# SIM808.net
KiCad netlist of a schematic drawn in Altium Designer
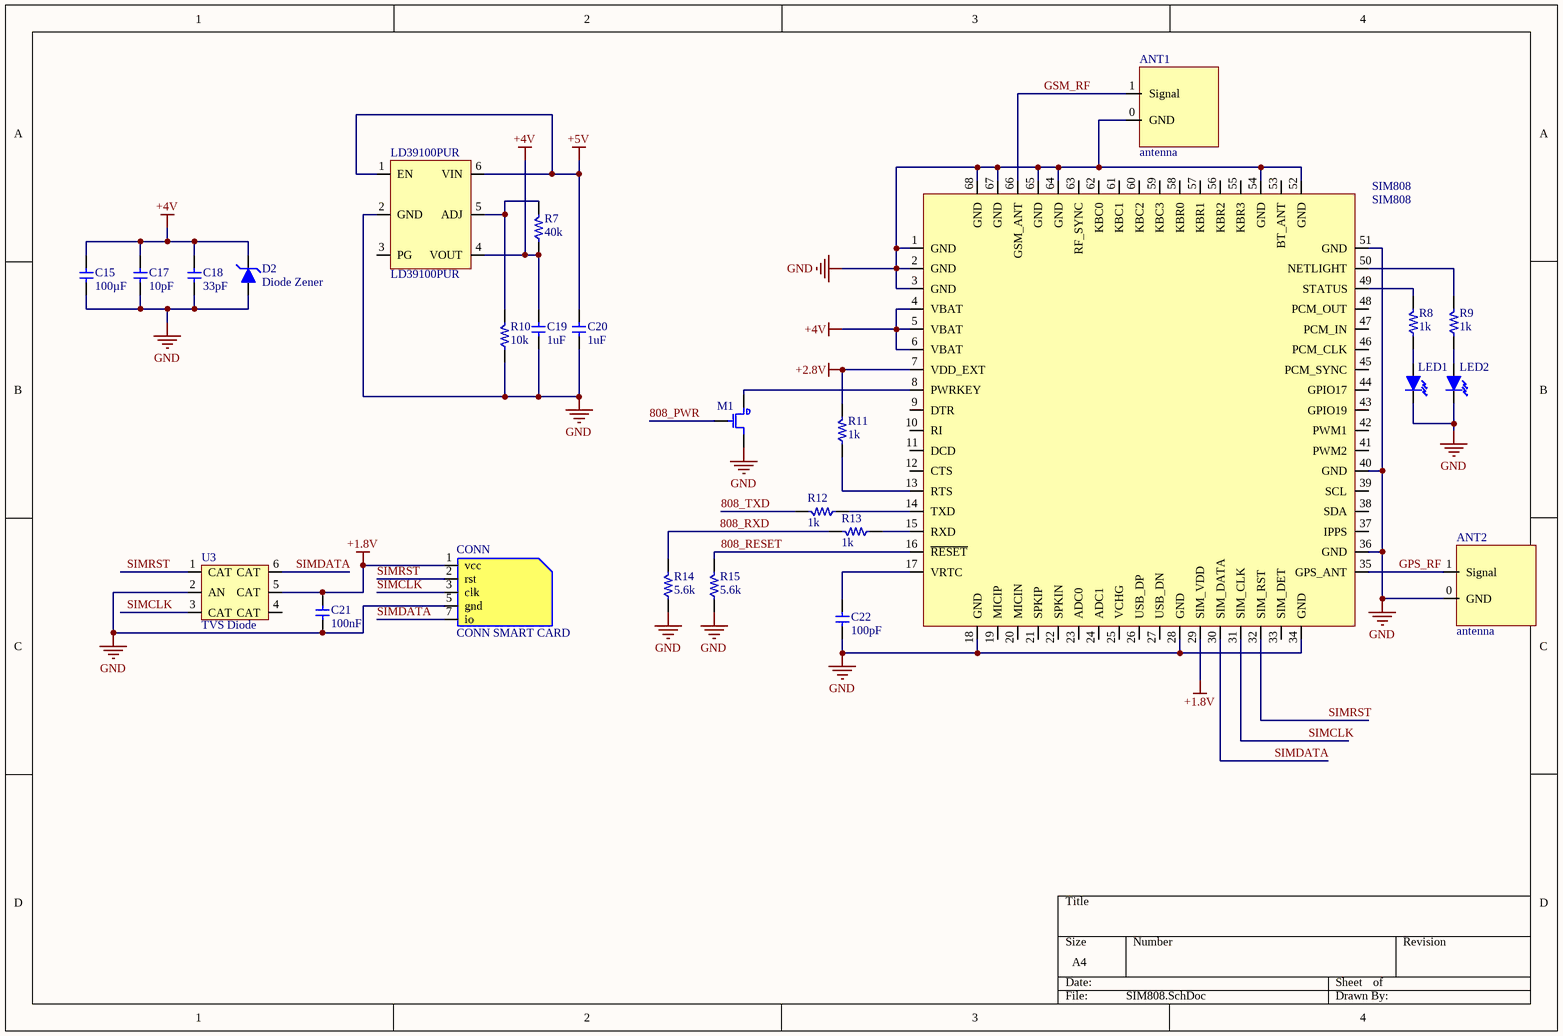
[diagram p0: SIM808.SchDoc]

(export (version "E")
  (design (tool "Eeschema 10.0.6"))
  (components
    (comp (ref "ANT1")
      (value "antenna")
      (footprint "uFL")
      (description "uFL SMT Antenna Connector")
      (fields (field (name "MFR") "adafruit"))
      (libsource (lib "uFLAntenna") (part "antenna"))
    )
    (comp (ref "ANT2")
      (value "antenna")
      (footprint "uFL")
      (description "uFL SMT Antenna Connector")
      (fields (field (name "MFR") "adafruit"))
      (libsource (lib "uFLAntenna") (part "antenna"))
    )
    (comp (ref "C15")
      (value "Cap Cer 100uF")
      (footprint "Cap 1210")
      (description "CAP CER 100UF 10V X5R 1210")
      (fields
        (field (name "MANUFACTURER") "Taiyo Yuden")
        (field (name "MANUFACTURER PART NUMBER") "LMK325ABJ107MM-P")
        (field (name "CAPACITANCE") "100µF")
      )
      (libsource (lib "SIM808") (part "LMK325ABJ107MM-P"))
    )
    (comp (ref "C17")
      (value "10pF")
      (footprint "0805")
      (description "Generic capacitor")
      (fields (field (name "Comment") "Generic Capacitor"))
      (libsource (lib "PowerCircuit") (part "Capacitor"))
    )
    (comp (ref "C18")
      (value "33pF")
      (footprint "0805")
      (description "Generic capacitor")
      (fields (field (name "Comment") "Generic Capacitor"))
      (libsource (lib "PowerCircuit") (part "Capacitor"))
    )
    (comp (ref "C19")
      (value "1uF")
      (footprint "0805")
      (description "Generic capacitor")
      (fields (field (name "Comment") "Generic Capacitor"))
      (libsource (lib "PowerCircuit") (part "Capacitor"))
    )
    (comp (ref "C20")
      (value "1uF")
      (footprint "0805")
      (description "Generic capacitor")
      (fields (field (name "Comment") "Generic Capacitor"))
      (libsource (lib "PowerCircuit") (part "Capacitor"))
    )
    (comp (ref "C21")
      (value "100nF")
      (footprint "0805")
      (description "Generic capacitor")
      (fields (field (name "Comment") "Generic Capacitor"))
      (libsource (lib "PowerCircuit") (part "Capacitor"))
    )
    (comp (ref "C22")
      (value "100pF")
      (footprint "0805")
      (description "Generic capacitor")
      (fields (field (name "Comment") "Generic Capacitor"))
      (libsource (lib "PowerCircuit") (part "Capacitor"))
    )
    (comp (ref "CONN")
      (value "CONN SMART CARD")
      (footprint "CONN SMART CARD")
      (fields
        (field (name "MANUFACTURER") "Wurth Electronics Inc")
        (field (name "MANUFACTURER PART NUMBER") "693022010811")
      )
      (libsource (lib "SIM808") (part "CONN SMART CARD"))
    )
    (comp (ref "D2")
      (value "Diode Zener")
      (footprint "Diode Zener")
      (description "DIODE ZENER 5.1V 500MW SOD123")
      (fields
        (field (name "MANUFACTURER") "ON Semiconductor")
        (field (name "MANUFACTURER PART NUMBER") "MMSZ5231BT1G")
      )
      (libsource (lib "SIM808") (part "MMSZ5231BT1G"))
    )
    (comp (ref "LD39100PUR")
      (value "LD39100PUR")
      (footprint "LD39100PUR")
      (description "Adjustable linear voltage regulator")
      (fields (field (name "MFR") "ST"))
      (libsource (lib "SIM808") (part "LD39100PUR"))
    )
    (comp (ref "LED1")
      (value "Led Red")
      (footprint "0805 LED")
      (description "LED RED CLEAR 0805 SMD")
      (fields
        (field (name "MANUFACTURER") "Lite-On Inc.")
        (field (name "MANUFACTURER PART NUMBER") "LTST-C171EKT")
      )
      (libsource (lib "SIM808") (part "LTST-C171EKT"))
    )
    (comp (ref "LED2")
      (value "Led Green")
      (footprint "0805 LED")
      (description "LED GREEN CLEAR 0805 SMD")
      (fields
        (field (name "MANUFACTURER") "Lite-On Inc.")
        (field (name "MANUFACTURER PART NUMBER") "LTST-C170GKT")
      )
      (libsource (lib "SIM808") (part "LTST-C170GKT"))
    )
    (comp (ref "M1")
      (value "N-CH Mosfet Switch")
      (footprint "SOT32-3")
      (description "MOSFET N-CH 20V 1.05A SOT23")
      (fields
        (field (name "MANUFACTURER") "NXP USA Inc.")
        (field (name "MANUFACTURER PART NUMBER") "BSH105,215")
      )
      (libsource (lib "SIM808") (part "BSH105,215"))
    )
    (comp (ref "R7")
      (value "40k")
      (footprint "0805")
      (description "Generic Resistor")
      (fields (field (name "Comment") "Resistor"))
      (libsource (lib "PowerCircuit") (part "Resistor"))
    )
    (comp (ref "R8")
      (value "1k")
      (footprint "0805")
      (description "Generic Resistor")
      (fields (field (name "Comment") "Resistor"))
      (libsource (lib "PowerCircuit") (part "Resistor"))
    )
    (comp (ref "R9")
      (value "1k")
      (footprint "0805")
      (description "Generic Resistor")
      (fields (field (name "Comment") "Resistor"))
      (libsource (lib "PowerCircuit") (part "Resistor"))
    )
    (comp (ref "R10")
      (value "10k")
      (footprint "0805")
      (description "Generic Resistor")
      (fields (field (name "Comment") "Resistor"))
      (libsource (lib "PowerCircuit") (part "Resistor"))
    )
    (comp (ref "R11")
      (value "1k")
      (footprint "0805")
      (description "Generic Resistor")
      (fields (field (name "Comment") "Resistor"))
      (libsource (lib "PowerCircuit") (part "Resistor"))
    )
    (comp (ref "R12")
      (value "1k")
      (footprint "0805")
      (description "Generic Resistor")
      (fields (field (name "Comment") "Resistor"))
      (libsource (lib "PowerCircuit") (part "Resistor"))
    )
    (comp (ref "R13")
      (value "1k")
      (footprint "0805")
      (description "Generic Resistor")
      (fields (field (name "Comment") "Resistor"))
      (libsource (lib "PowerCircuit") (part "Resistor"))
    )
    (comp (ref "R14")
      (value "5.6k")
      (footprint "0805")
      (description "Generic Resistor")
      (fields (field (name "Comment") "Resistor"))
      (libsource (lib "PowerCircuit") (part "Resistor"))
    )
    (comp (ref "R15")
      (value "5.6k")
      (footprint "0805")
      (description "Generic Resistor")
      (fields (field (name "Comment") "Resistor"))
      (libsource (lib "PowerCircuit") (part "Resistor"))
    )
    (comp (ref "SIM808")
      (value "SIM808")
      (footprint "SIM808")
      (description "SIM808 GSM + GPRS + GPS Cellular Module")
      (fields (field (name "MFR") "SimCom"))
      (libsource (lib "SIM808") (part "SIM808"))
    )
    (comp (ref "U3")
      (value "TVS Diode")
      (footprint "SMF05CT2G")
      (description "TVS DIODE 5VWM 12.5VC SOT363")
      (fields
        (field (name "MANUFACTURER") "ON Semiconductor")
        (field (name "MANUFACTURER PART NUMBER") "SMF05CT2G")
      )
      (libsource (lib "SIM808") (part "SMF05CT2G"))
    )
  )
  (nets
    (net (code "1") (name "+1.8V") (class "Default")
      (node (ref "C21") (pin "1") (pinfunction "1_1") (pintype "passive"))
      (node (ref "CONN") (pin "1") (pinfunction "vcc_1") (pintype "passive"))
      (node (ref "SIM808") (pin "29") (pinfunction "SIM_VDD_29") (pintype "passive"))
      (node (ref "U3") (pin "5") (pinfunction "CAT_5") (pintype "passive"))
    )
    (net (code "2") (name "+2.8V") (class "Default")
      (node (ref "R11") (pin "2") (pinfunction "2_2") (pintype "passive"))
      (node (ref "SIM808") (pin "7") (pinfunction "VDD_EXT_7") (pintype "passive"))
    )
    (net (code "3") (name "+4V") (class "Default")
      (node (ref "C15") (pin "1") (pinfunction "1_1") (pintype "passive"))
      (node (ref "C17") (pin "1") (pinfunction "1_1") (pintype "passive"))
      (node (ref "C18") (pin "1") (pinfunction "1_1") (pintype "passive"))
      (node (ref "C19") (pin "2") (pinfunction "2_2") (pintype "passive"))
      (node (ref "D2") (pin "1") (pinfunction "1_1") (pintype "passive"))
      (node (ref "LD39100PUR") (pin "4") (pinfunction "VOUT_4") (pintype "passive"))
      (node (ref "R7") (pin "1") (pinfunction "1_1") (pintype "passive"))
      (node (ref "SIM808") (pin "4") (pinfunction "VBAT_4") (pintype "passive"))
      (node (ref "SIM808") (pin "5") (pinfunction "VBAT_5") (pintype "passive"))
      (node (ref "SIM808") (pin "6") (pinfunction "VBAT_6") (pintype "passive"))
    )
    (net (code "4") (name "+5V") (class "Default")
      (node (ref "C20") (pin "1") (pinfunction "1_1") (pintype "passive"))
      (node (ref "LD39100PUR") (pin "1") (pinfunction "EN_1") (pintype "passive"))
      (node (ref "LD39100PUR") (pin "6") (pinfunction "VIN_6") (pintype "passive"))
    )
    (net (code "5") (name "/808_PWR") (class "Default")
      (node (ref "M1") (pin "1") (pinfunction "G_1") (pintype "passive"))
    )
    (net (code "6") (name "/808_RESET") (class "Default")
      (node (ref "R15") (pin "2") (pinfunction "2_2") (pintype "passive"))
      (node (ref "SIM808") (pin "16") (pinfunction "~{RESET}_16") (pintype "passive"))
    )
    (net (code "7") (name "/808_RXD") (class "Default")
      (node (ref "R13") (pin "2") (pinfunction "2_2") (pintype "passive"))
      (node (ref "R14") (pin "2") (pinfunction "2_2") (pintype "passive"))
    )
    (net (code "8") (name "/808_TXD") (class "Default")
      (node (ref "R12") (pin "2") (pinfunction "2_2") (pintype "passive"))
    )
    (net (code "9") (name "/GPS_RF") (class "Default")
      (node (ref "ANT2") (pin "1") (pinfunction "Signal_1") (pintype "passive"))
      (node (ref "SIM808") (pin "35") (pinfunction "GPS_ANT_35") (pintype "passive"))
    )
    (net (code "10") (name "/GSM_RF") (class "Default")
      (node (ref "ANT1") (pin "1") (pinfunction "Signal_1") (pintype "passive"))
      (node (ref "SIM808") (pin "66") (pinfunction "GSM_ANT_66") (pintype "passive"))
    )
    (net (code "11") (name "/SIMCLK") (class "Default")
      (node (ref "CONN") (pin "3") (pinfunction "clk_3") (pintype "passive"))
      (node (ref "SIM808") (pin "31") (pinfunction "SIM_CLK_31") (pintype "passive"))
      (node (ref "U3") (pin "3") (pinfunction "CAT_3") (pintype "passive"))
    )
    (net (code "12") (name "/SIMDATA") (class "Default")
      (node (ref "CONN") (pin "7") (pinfunction "io_7") (pintype "passive"))
      (node (ref "SIM808") (pin "30") (pinfunction "SIM_DATA_30") (pintype "passive"))
      (node (ref "U3") (pin "6") (pinfunction "CAT_6") (pintype "passive"))
    )
    (net (code "13") (name "/SIMRST") (class "Default")
      (node (ref "CONN") (pin "2") (pinfunction "rst_2") (pintype "passive"))
      (node (ref "SIM808") (pin "32") (pinfunction "SIM_RST_32") (pintype "passive"))
      (node (ref "U3") (pin "1") (pinfunction "CAT_1") (pintype "passive"))
    )
    (net (code "14") (name "GND") (class "Default")
      (node (ref "ANT1") (pin "0") (pinfunction "GND_0") (pintype "passive"))
      (node (ref "ANT2") (pin "0") (pinfunction "GND_0") (pintype "passive"))
      (node (ref "C15") (pin "2") (pinfunction "2_2") (pintype "passive"))
      (node (ref "C17") (pin "2") (pinfunction "2_2") (pintype "passive"))
      (node (ref "C18") (pin "2") (pinfunction "2_2") (pintype "passive"))
      (node (ref "C19") (pin "1") (pinfunction "1_1") (pintype "passive"))
      (node (ref "C20") (pin "2") (pinfunction "2_2") (pintype "passive"))
      (node (ref "C21") (pin "2") (pinfunction "2_2") (pintype "passive"))
      (node (ref "C22") (pin "2") (pinfunction "2_2") (pintype "passive"))
      (node (ref "CONN") (pin "5") (pinfunction "gnd_5") (pintype "passive"))
      (node (ref "D2") (pin "2") (pinfunction "2_2") (pintype "passive"))
      (node (ref "LD39100PUR") (pin "2") (pinfunction "GND_2") (pintype "passive"))
      (node (ref "LED1") (pin "1") (pinfunction "1_1") (pintype "passive"))
      (node (ref "LED2") (pin "1") (pinfunction "1_1") (pintype "passive"))
      (node (ref "M1") (pin "2") (pinfunction "S_2") (pintype "passive"))
      (node (ref "R10") (pin "1") (pinfunction "1_1") (pintype "passive"))
      (node (ref "R14") (pin "1") (pinfunction "1_1") (pintype "passive"))
      (node (ref "R15") (pin "1") (pinfunction "1_1") (pintype "passive"))
      (node (ref "SIM808") (pin "1") (pinfunction "GND_1") (pintype "passive"))
      (node (ref "SIM808") (pin "18") (pinfunction "GND_18") (pintype "passive"))
      (node (ref "SIM808") (pin "2") (pinfunction "GND_2") (pintype "passive"))
      (node (ref "SIM808") (pin "28") (pinfunction "GND_28") (pintype "passive"))
      (node (ref "SIM808") (pin "3") (pinfunction "GND_3") (pintype "passive"))
      (node (ref "SIM808") (pin "34") (pinfunction "GND_34") (pintype "passive"))
      (node (ref "SIM808") (pin "36") (pinfunction "GND_36") (pintype "passive"))
      (node (ref "SIM808") (pin "40") (pinfunction "GND_40") (pintype "passive"))
      (node (ref "SIM808") (pin "51") (pinfunction "GND_51") (pintype "passive"))
      (node (ref "SIM808") (pin "52") (pinfunction "GND_52") (pintype "passive"))
      (node (ref "SIM808") (pin "54") (pinfunction "GND_54") (pintype "passive"))
      (node (ref "SIM808") (pin "64") (pinfunction "GND_64") (pintype "passive"))
      (node (ref "SIM808") (pin "65") (pinfunction "GND_65") (pintype "passive"))
      (node (ref "SIM808") (pin "67") (pinfunction "GND_67") (pintype "passive"))
      (node (ref "SIM808") (pin "68") (pinfunction "GND_68") (pintype "passive"))
      (node (ref "U3") (pin "2") (pinfunction "AN_2") (pintype "passive"))
    )
    (net (code "15") (name "Net-(LD39100PUR-ADJ)") (class "Default")
      (node (ref "LD39100PUR") (pin "5") (pinfunction "ADJ_5") (pintype "passive"))
      (node (ref "R10") (pin "2") (pinfunction "2_2") (pintype "passive"))
      (node (ref "R7") (pin "2") (pinfunction "2_2") (pintype "passive"))
    )
    (net (code "16") (name "Net-(LED1-Pad2)") (class "Default")
      (node (ref "LED1") (pin "2") (pinfunction "2_2") (pintype "passive"))
      (node (ref "R8") (pin "1") (pinfunction "1_1") (pintype "passive"))
    )
    (net (code "17") (name "Net-(LED2-Pad2)") (class "Default")
      (node (ref "LED2") (pin "2") (pinfunction "2_2") (pintype "passive"))
      (node (ref "R9") (pin "1") (pinfunction "1_1") (pintype "passive"))
    )
    (net (code "18") (name "Net-(M1-D)") (class "Default")
      (node (ref "M1") (pin "3") (pinfunction "D_3") (pintype "passive"))
      (node (ref "SIM808") (pin "8") (pinfunction "PWRKEY_8") (pintype "passive"))
    )
    (net (code "19") (name "Net-(SIM808-NETLIGHT)") (class "Default")
      (node (ref "R9") (pin "2") (pinfunction "2_2") (pintype "passive"))
      (node (ref "SIM808") (pin "50") (pinfunction "NETLIGHT_50") (pintype "passive"))
    )
    (net (code "20") (name "Net-(SIM808-RTS)") (class "Default")
      (node (ref "R11") (pin "1") (pinfunction "1_1") (pintype "passive"))
      (node (ref "SIM808") (pin "13") (pinfunction "RTS_13") (pintype "passive"))
    )
    (net (code "21") (name "Net-(SIM808-RXD)") (class "Default")
      (node (ref "R13") (pin "1") (pinfunction "1_1") (pintype "passive"))
      (node (ref "SIM808") (pin "15") (pinfunction "RXD_15") (pintype "passive"))
    )
    (net (code "22") (name "Net-(SIM808-STATUS)") (class "Default")
      (node (ref "R8") (pin "2") (pinfunction "2_2") (pintype "passive"))
      (node (ref "SIM808") (pin "49") (pinfunction "STATUS_49") (pintype "passive"))
    )
    (net (code "23") (name "Net-(SIM808-TXD)") (class "Default")
      (node (ref "R12") (pin "1") (pinfunction "1_1") (pintype "passive"))
      (node (ref "SIM808") (pin "14") (pinfunction "TXD_14") (pintype "passive"))
    )
    (net (code "24") (name "Net-(SIM808-VRTC)") (class "Default")
      (node (ref "C22") (pin "1") (pinfunction "1_1") (pintype "passive"))
      (node (ref "SIM808") (pin "17") (pinfunction "VRTC_17") (pintype "passive"))
    )
    (net (code "25") (name "unconnected-(LD39100PUR-PG-Pad3)") (class "Default")
      (node (ref "LD39100PUR") (pin "3") (pinfunction "PG_3") (pintype "passive"))
    )
    (net (code "26") (name "unconnected-(SIM808-ADC0-Pad23)") (class "Default")
      (node (ref "SIM808") (pin "23") (pinfunction "ADC0_23") (pintype "passive"))
    )
    (net (code "27") (name "unconnected-(SIM808-ADC1-Pad24)") (class "Default")
      (node (ref "SIM808") (pin "24") (pinfunction "ADC1_24") (pintype "passive"))
    )
    (net (code "28") (name "unconnected-(SIM808-BT_ANT-Pad53)") (class "Default")
      (node (ref "SIM808") (pin "53") (pinfunction "BT_ANT_53") (pintype "passive"))
    )
    (net (code "29") (name "unconnected-(SIM808-CTS-Pad12)") (class "Default")
      (node (ref "SIM808") (pin "12") (pinfunction "CTS_12") (pintype "passive"))
    )
    (net (code "30") (name "unconnected-(SIM808-DCD-Pad11)") (class "Default")
      (node (ref "SIM808") (pin "11") (pinfunction "DCD_11") (pintype "passive"))
    )
    (net (code "31") (name "unconnected-(SIM808-DTR-Pad9)") (class "Default")
      (node (ref "SIM808") (pin "9") (pinfunction "DTR_9") (pintype "passive"))
    )
    (net (code "32") (name "unconnected-(SIM808-GPIO17-Pad44)") (class "Default")
      (node (ref "SIM808") (pin "44") (pinfunction "GPIO17_44") (pintype "passive"))
    )
    (net (code "33") (name "unconnected-(SIM808-GPIO19-Pad43)") (class "Default")
      (node (ref "SIM808") (pin "43") (pinfunction "GPIO19_43") (pintype "passive"))
    )
    (net (code "34") (name "unconnected-(SIM808-IPPS-Pad37)") (class "Default")
      (node (ref "SIM808") (pin "37") (pinfunction "IPPS_37") (pintype "passive"))
    )
    (net (code "35") (name "unconnected-(SIM808-KBC0-Pad62)") (class "Default")
      (node (ref "SIM808") (pin "62") (pinfunction "KBC0_62") (pintype "passive"))
    )
    (net (code "36") (name "unconnected-(SIM808-KBC1-Pad61)") (class "Default")
      (node (ref "SIM808") (pin "61") (pinfunction "KBC1_61") (pintype "passive"))
    )
    (net (code "37") (name "unconnected-(SIM808-KBC2-Pad60)") (class "Default")
      (node (ref "SIM808") (pin "60") (pinfunction "KBC2_60") (pintype "passive"))
    )
    (net (code "38") (name "unconnected-(SIM808-KBC3-Pad59)") (class "Default")
      (node (ref "SIM808") (pin "59") (pinfunction "KBC3_59") (pintype "passive"))
    )
    (net (code "39") (name "unconnected-(SIM808-KBR0-Pad58)") (class "Default")
      (node (ref "SIM808") (pin "58") (pinfunction "KBR0_58") (pintype "passive"))
    )
    (net (code "40") (name "unconnected-(SIM808-KBR1-Pad57)") (class "Default")
      (node (ref "SIM808") (pin "57") (pinfunction "KBR1_57") (pintype "passive"))
    )
    (net (code "41") (name "unconnected-(SIM808-KBR2-Pad56)") (class "Default")
      (node (ref "SIM808") (pin "56") (pinfunction "KBR2_56") (pintype "passive"))
    )
    (net (code "42") (name "unconnected-(SIM808-KBR3-Pad55)") (class "Default")
      (node (ref "SIM808") (pin "55") (pinfunction "KBR3_55") (pintype "passive"))
    )
    (net (code "43") (name "unconnected-(SIM808-MICIN-Pad20)") (class "Default")
      (node (ref "SIM808") (pin "20") (pinfunction "MICIN_20") (pintype "passive"))
    )
    (net (code "44") (name "unconnected-(SIM808-MICIP-Pad19)") (class "Default")
      (node (ref "SIM808") (pin "19") (pinfunction "MICIP_19") (pintype "passive"))
    )
    (net (code "45") (name "unconnected-(SIM808-PCM_CLK-Pad46)") (class "Default")
      (node (ref "SIM808") (pin "46") (pinfunction "PCM_CLK_46") (pintype "passive"))
    )
    (net (code "46") (name "unconnected-(SIM808-PCM_IN-Pad47)") (class "Default")
      (node (ref "SIM808") (pin "47") (pinfunction "PCM_IN_47") (pintype "passive"))
    )
    (net (code "47") (name "unconnected-(SIM808-PCM_OUT-Pad48)") (class "Default")
      (node (ref "SIM808") (pin "48") (pinfunction "PCM_OUT_48") (pintype "passive"))
    )
    (net (code "48") (name "unconnected-(SIM808-PCM_SYNC-Pad45)") (class "Default")
      (node (ref "SIM808") (pin "45") (pinfunction "PCM_SYNC_45") (pintype "passive"))
    )
    (net (code "49") (name "unconnected-(SIM808-PWM1-Pad42)") (class "Default")
      (node (ref "SIM808") (pin "42") (pinfunction "PWM1_42") (pintype "passive"))
    )
    (net (code "50") (name "unconnected-(SIM808-PWM2-Pad41)") (class "Default")
      (node (ref "SIM808") (pin "41") (pinfunction "PWM2_41") (pintype "passive"))
    )
    (net (code "51") (name "unconnected-(SIM808-RF_SYNC-Pad63)") (class "Default")
      (node (ref "SIM808") (pin "63") (pinfunction "RF_SYNC_63") (pintype "passive"))
    )
    (net (code "52") (name "unconnected-(SIM808-RI-Pad10)") (class "Default")
      (node (ref "SIM808") (pin "10") (pinfunction "RI_10") (pintype "passive"))
    )
    (net (code "53") (name "unconnected-(SIM808-SCL-Pad39)") (class "Default")
      (node (ref "SIM808") (pin "39") (pinfunction "SCL_39") (pintype "passive"))
    )
    (net (code "54") (name "unconnected-(SIM808-SDA-Pad38)") (class "Default")
      (node (ref "SIM808") (pin "38") (pinfunction "SDA_38") (pintype "passive"))
    )
    (net (code "55") (name "unconnected-(SIM808-SIM_DET-Pad33)") (class "Default")
      (node (ref "SIM808") (pin "33") (pinfunction "SIM_DET_33") (pintype "passive"))
    )
    (net (code "56") (name "unconnected-(SIM808-SPKIN-Pad22)") (class "Default")
      (node (ref "SIM808") (pin "22") (pinfunction "SPKIN_22") (pintype "passive"))
    )
    (net (code "57") (name "unconnected-(SIM808-SPKIP-Pad21)") (class "Default")
      (node (ref "SIM808") (pin "21") (pinfunction "SPKIP_21") (pintype "passive"))
    )
    (net (code "58") (name "unconnected-(SIM808-USB_DN-Pad27)") (class "Default")
      (node (ref "SIM808") (pin "27") (pinfunction "USB_DN_27") (pintype "passive"))
    )
    (net (code "59") (name "unconnected-(SIM808-USB_DP-Pad26)") (class "Default")
      (node (ref "SIM808") (pin "26") (pinfunction "USB_DP_26") (pintype "passive"))
    )
    (net (code "60") (name "unconnected-(SIM808-VCHG-Pad25)") (class "Default")
      (node (ref "SIM808") (pin "25") (pinfunction "VCHG_25") (pintype "passive"))
    )
    (net (code "61") (name "unconnected-(U3-CAT-Pad4)") (class "Default")
      (node (ref "U3") (pin "4") (pinfunction "CAT_4") (pintype "passive"))
    )
  )
)
